# MCU.net
KiCad netlist of a schematic drawn in Altium Designer
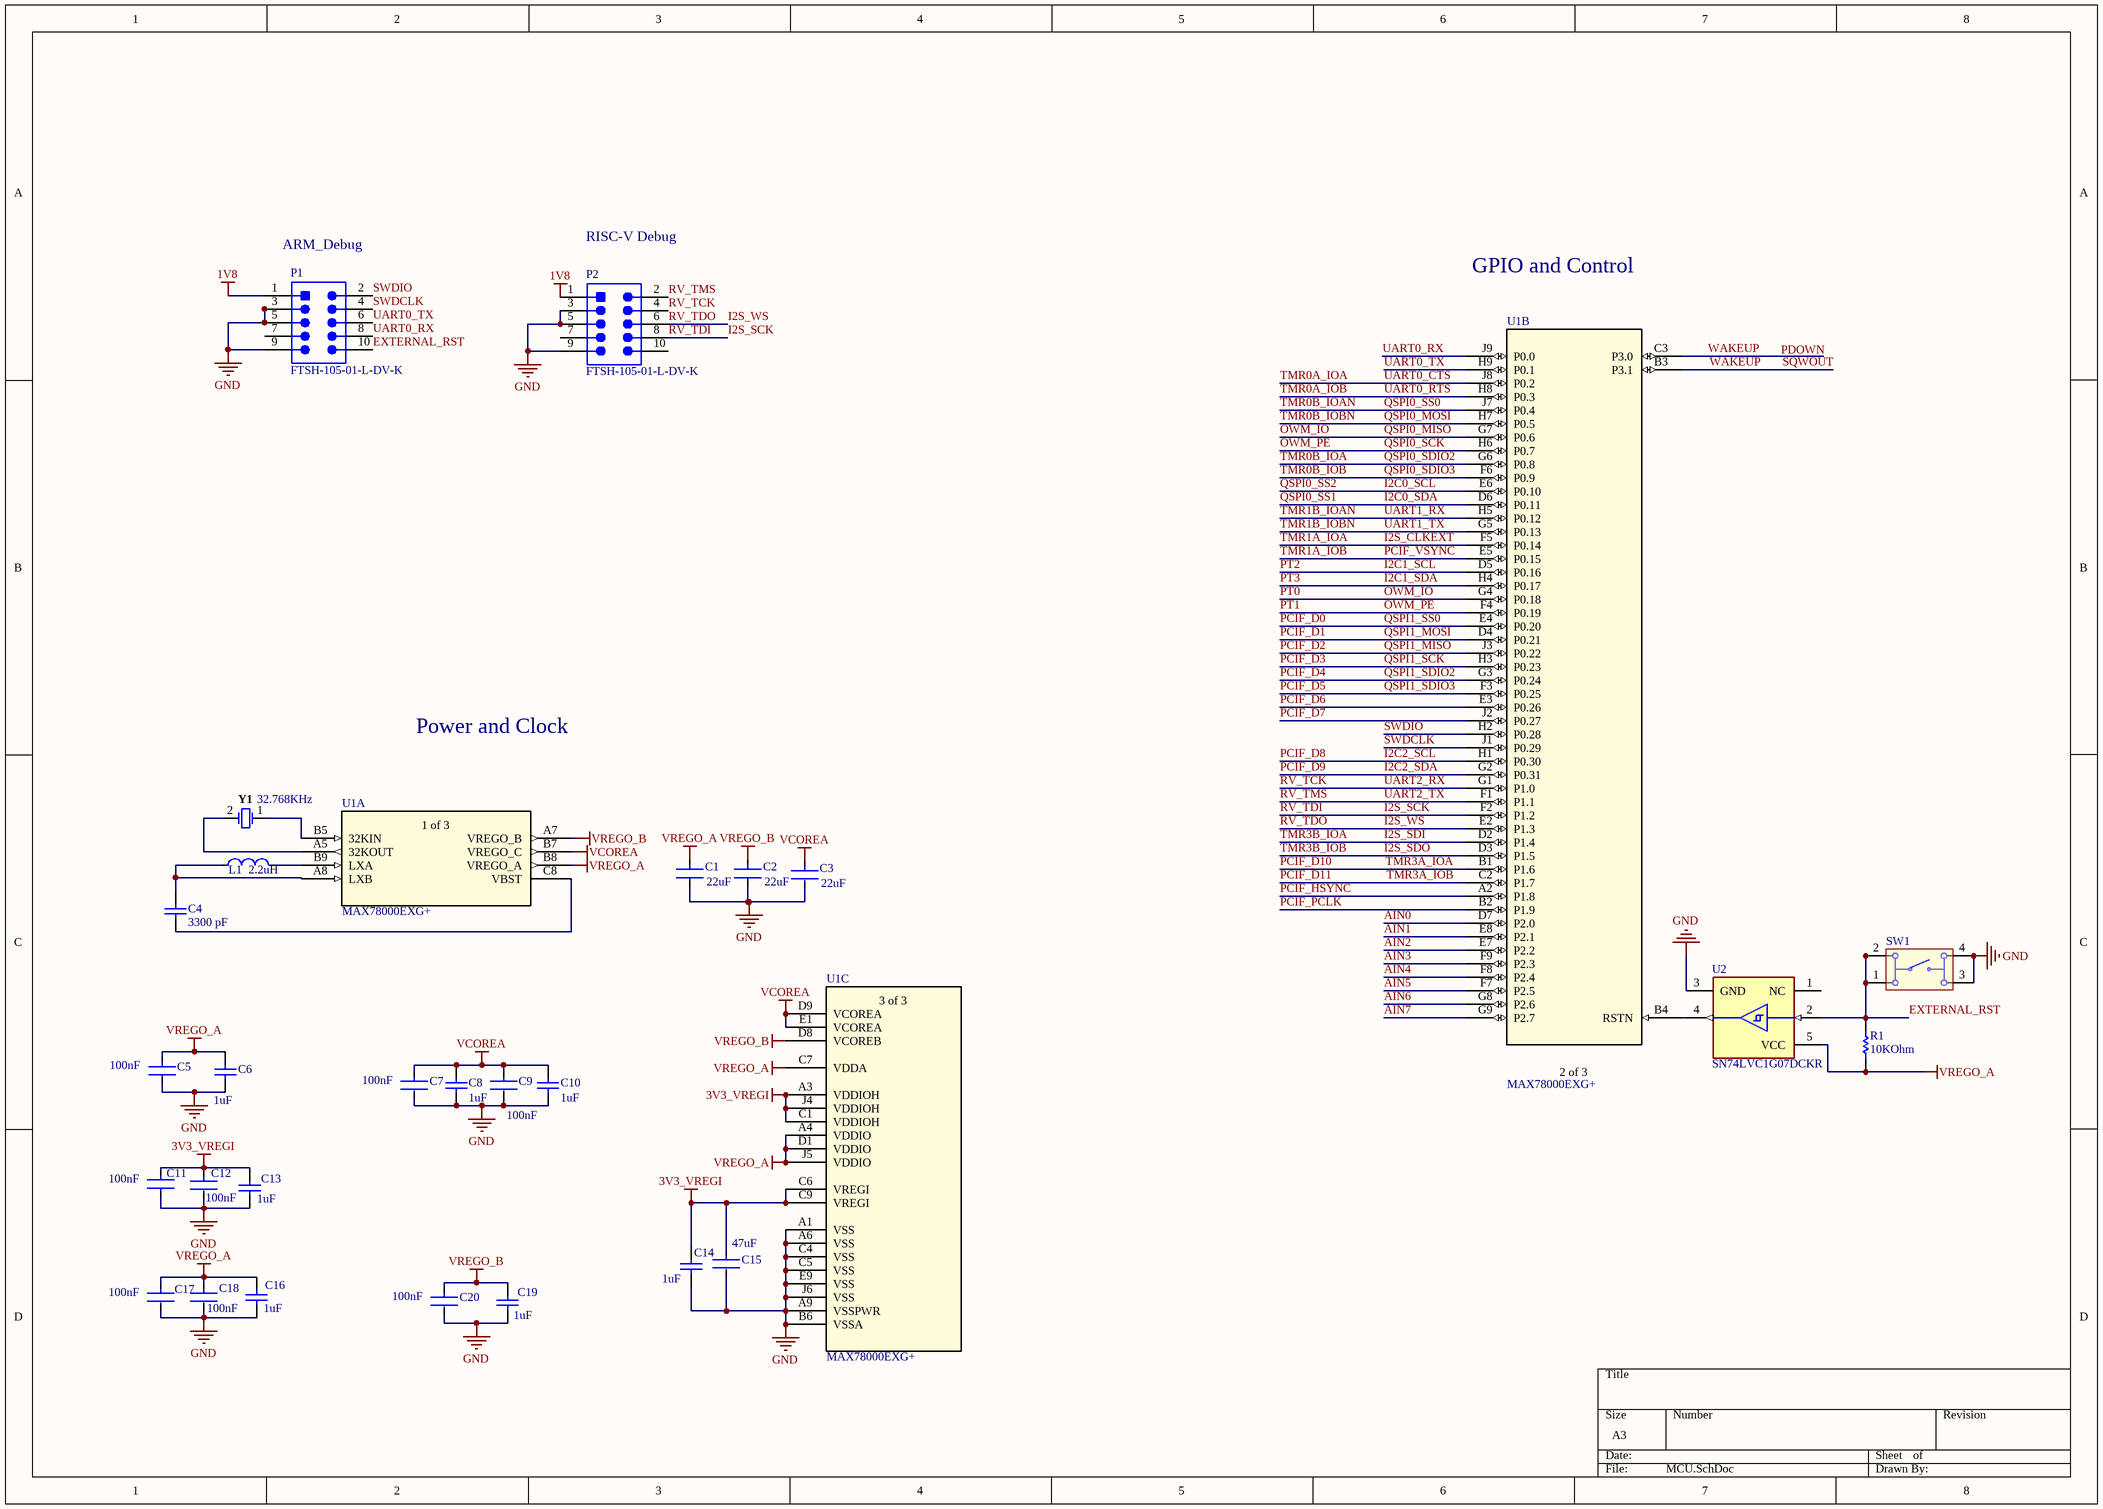
[diagram p0: MCU.SchDoc]

(export (version "E")
  (design (tool "Eeschema 10.0.6"))
  (components
    (comp (ref "C1")
      (value "CL10A226MO7JZNC")
      (footprint "FP-CL10-IPC_A")
      (description "Cap Ceramic 22uF 16V X5R ±20% Pad SMD 0603 +85°C T/R")
      (fields (field (name "CAPACITANCE") "22uF") (field (name "TOLERANCE") "20%"))
      (libsource (lib "Altium Content Vault") (part "b4654b650e69147ec39a6b967a45e02"))
    )
    (comp (ref "C2")
      (value "CL10A226MO7JZNC")
      (footprint "FP-CL10-IPC_A")
      (description "Cap Ceramic 22uF 16V X5R ±20% Pad SMD 0603 +85°C T/R")
      (fields (field (name "CAPACITANCE") "22uF") (field (name "TOLERANCE") "20%"))
      (libsource (lib "Altium Content Vault") (part "b4654b650e69147ec39a6b967a45e02"))
    )
    (comp (ref "C3")
      (value "CL10A226MO7JZNC")
      (footprint "FP-CL10-IPC_A")
      (description "Cap Ceramic 22uF 16V X5R ±20% Pad SMD 0603 +85°C T/R")
      (fields (field (name "CAPACITANCE") "22uF") (field (name "TOLERANCE") "20%"))
      (libsource (lib "Altium Content Vault") (part "b4654b650e69147ec39a6b967a45e02"))
    )
    (comp (ref "C4")
      (value "3300 pF")
      (footprint "CAPC1005X55X25ML05T10")
      (fields (field (name "MANUFACTURER") "Murata") (field (name "PART NUMBER") "GRM155R71H332KA01D"))
      (libsource (lib "Altium Content Vault") (part "CAP"))
    )
    (comp (ref "C5")
      (value "GRM033R61C104KE14D")
      (footprint "FP-GRM033-0_03-MFG")
      (description "Chip Multilayer Ceramic Capacitors for General Purpose, 0201, 0.10uF, X5R, 15%, 10%, 16V")
      (fields (field (name "TOLERANCE") "10%") (field (name "CAPACITANCE") "100nF"))
      (libsource (lib "Altium Content Vault") (part "b4654b650e69147ec39a6b967a45e02"))
    )
    (comp (ref "C6")
      (value "1uF")
      (footprint "CAPC1005X60X30LL05T10")
      (fields (field (name "PART NUMBER") "C0402C105K8PAC7867") (field (name "MANUFACTURER") "Kemet"))
      (libsource (lib "Altium Content Vault") (part "CAP"))
    )
    (comp (ref "C7")
      (value "GRM033R61C104KE14D")
      (footprint "FP-GRM033-0_03-MFG")
      (description "Chip Multilayer Ceramic Capacitors for General Purpose, 0201, 0.10uF, X5R, 15%, 10%, 16V")
      (fields (field (name "TOLERANCE") "10%") (field (name "CAPACITANCE") "100nF"))
      (libsource (lib "Altium Content Vault") (part "b4654b650e69147ec39a6b967a45e02"))
    )
    (comp (ref "C8")
      (value "1uF")
      (footprint "CAPC1005X60X30LL05T10")
      (fields (field (name "PART NUMBER") "C0402C105K8PAC7867") (field (name "MANUFACTURER") "Kemet"))
      (libsource (lib "Altium Content Vault") (part "CAP"))
    )
    (comp (ref "C9")
      (value "GRM033R61C104KE14D")
      (footprint "FP-GRM033-0_03-MFG")
      (description "Chip Multilayer Ceramic Capacitors for General Purpose, 0201, 0.10uF, X5R, 15%, 10%, 16V")
      (fields (field (name "TOLERANCE") "10%") (field (name "CAPACITANCE") "100nF"))
      (libsource (lib "Altium Content Vault") (part "b4654b650e69147ec39a6b967a45e02"))
    )
    (comp (ref "C10")
      (value "1uF")
      (footprint "CAPC1005X60X30LL05T10")
      (fields (field (name "PART NUMBER") "C0402C105K8PAC7867") (field (name "MANUFACTURER") "Kemet"))
      (libsource (lib "Altium Content Vault") (part "CAP"))
    )
    (comp (ref "C11")
      (value "GRM033R61C104KE14D")
      (footprint "FP-GRM033-0_03-MFG")
      (description "Chip Multilayer Ceramic Capacitors for General Purpose, 0201, 0.10uF, X5R, 15%, 10%, 16V")
      (fields (field (name "TOLERANCE") "10%") (field (name "CAPACITANCE") "100nF"))
      (libsource (lib "Altium Content Vault") (part "b4654b650e69147ec39a6b967a45e02"))
    )
    (comp (ref "C12")
      (value "GRM033R61C104KE14D")
      (footprint "FP-GRM033-0_03-MFG")
      (description "Chip Multilayer Ceramic Capacitors for General Purpose, 0201, 0.10uF, X5R, 15%, 10%, 16V")
      (fields (field (name "TOLERANCE") "10%") (field (name "CAPACITANCE") "100nF"))
      (libsource (lib "Altium Content Vault") (part "b4654b650e69147ec39a6b967a45e02"))
    )
    (comp (ref "C13")
      (value "1uF")
      (footprint "CAPC1005X60X30LL05T10")
      (fields (field (name "PART NUMBER") "C0402C105K8PAC7867") (field (name "MANUFACTURER") "Kemet"))
      (libsource (lib "Altium Content Vault") (part "CAP"))
    )
    (comp (ref "C14")
      (value "1uF")
      (footprint "CAPC1005X60X30LL05T10")
      (fields (field (name "PART NUMBER") "C0402C105K8PAC7867") (field (name "MANUFACTURER") "Kemet"))
      (libsource (lib "Altium Content Vault") (part "CAP"))
    )
    (comp (ref "C15")
      (value "GRM21BR61A476ME15K")
      (footprint "FP-GRM21B-0_2-e0_2_0_7-IPC_B")
      (description "Chip Multilayer Ceramic Capacitors for General Purpose, 0805, 47uF, X5R, 15%, 20%, 10V")
      (fields (field (name "TOLERANCE") "20%") (field (name "CAPACITANCE") "47uF"))
      (libsource (lib "Altium Content Vault") (part "b4654b650e69147ec39a6b967a45e02"))
    )
    (comp (ref "C16")
      (value "1uF")
      (footprint "CAPC1005X60X30LL05T10")
      (fields (field (name "PART NUMBER") "C0402C105K8PAC7867") (field (name "MANUFACTURER") "Kemet"))
      (libsource (lib "Altium Content Vault") (part "CAP"))
    )
    (comp (ref "C17")
      (value "GRM033R61C104KE14D")
      (footprint "FP-GRM033-0_03-MFG")
      (description "Chip Multilayer Ceramic Capacitors for General Purpose, 0201, 0.10uF, X5R, 15%, 10%, 16V")
      (fields (field (name "TOLERANCE") "10%") (field (name "CAPACITANCE") "100nF"))
      (libsource (lib "Altium Content Vault") (part "b4654b650e69147ec39a6b967a45e02"))
    )
    (comp (ref "C18")
      (value "GRM033R61C104KE14D")
      (footprint "FP-GRM033-0_03-MFG")
      (description "Chip Multilayer Ceramic Capacitors for General Purpose, 0201, 0.10uF, X5R, 15%, 10%, 16V")
      (fields (field (name "TOLERANCE") "10%") (field (name "CAPACITANCE") "100nF"))
      (libsource (lib "Altium Content Vault") (part "b4654b650e69147ec39a6b967a45e02"))
    )
    (comp (ref "C19")
      (value "1uF")
      (footprint "CAPC1005X60X30LL05T10")
      (fields (field (name "PART NUMBER") "C0402C105K8PAC7867") (field (name "MANUFACTURER") "Kemet"))
      (libsource (lib "Altium Content Vault") (part "CAP"))
    )
    (comp (ref "C20")
      (value "GRM033R61C104KE14D")
      (footprint "FP-GRM033-0_03-MFG")
      (description "Chip Multilayer Ceramic Capacitors for General Purpose, 0201, 0.10uF, X5R, 15%, 10%, 16V")
      (fields (field (name "TOLERANCE") "10%") (field (name "CAPACITANCE") "100nF"))
      (libsource (lib "Altium Content Vault") (part "b4654b650e69147ec39a6b967a45e02"))
    )
    (comp (ref "L1")
      (value "MLP2012H2R2MT0S1")
      (footprint "FP-MLP2012M-IPC_C")
      (description "Shielded Multilayer Inductor 2.2uH ±20% 1000mA 195mΩ SMD 0805")
      (fields (field (name "TOLERANCE") "20%") (field (name "INDUCTANCE") "2.2uH"))
      (libsource (lib "Altium Content Vault") (part "725321dda6339637d4d059423bc1c3c"))
    )
    (comp (ref "P1")
      (value "FTSH-105-01-L-DV-K")
      (footprint "SMTC-FTSH-105-01-L-DV-K_V")
      (description "Male Header, Pitch 1.27 mm, 2 x 5 Position, Height 6.25 mm")
      (fields (field (name "MANUFACTURER") "Samtec"))
      (libsource (lib "Altium Content Vault") (part "CN-2P-M-R10"))
    )
    (comp (ref "P2")
      (value "FTSH-105-01-L-DV-K")
      (footprint "SMTC-FTSH-105-01-L-DV-K_V")
      (description "Male Header, Pitch 1.27 mm, 2 x 5 Position, Height 6.25 mm")
      (fields (field (name "MANUFACTURER") "Samtec"))
      (libsource (lib "Altium Content Vault") (part "CN-2P-M-R10"))
    )
    (comp (ref "R1")
      (value "ERJ3EKF1002V")
      (footprint "RESC1609X55X30LL15T15")
      (description "Chip Resistor, 10 KOhm, +/- 1%, 0.1 W, -55 to 155 degC, 0603 (1608 Metric), RoHS, Tape and Reel")
      (fields
        (field (name "RESISTANCE") "10KOhm")
        (field (name "TOLERANCE") "1%")
        (field (name "MANUFACTURER") "Panasonic")
      )
      (libsource (lib "Altium Content Vault") (part "RES-2"))
    )
    (comp (ref "SW1")
      (value "430481025816")
      (footprint "430481025816")
      (description "WS-TASV SMD Tact Switch 6X6 mm")
      (fields (field (name "MANUFACTURER") "Wuerth Elektronik"))
      (libsource (lib "Altium Content Vault") (part "WE-TACT-SW-4_A"))
    )
    (comp (ref "U1")
      (value "MAX78000EXG+")
      (footprint "21-0735_MXM")
      (description "No Description Available")
      (fields (field (name "COPYRIGHT") "Copyright (C) 2018 Accelerated Designs. All rights reserved"))
      (libsource (lib "2021-06-08_17-56-01") (part "MAX78000EXG+"))
    )
    (comp (ref "U2")
      (value "SN74LVC1G07DCKR")
      (footprint "FP-DCK0005A-IPC_C")
      (description "IC BUFF/DVR NON-INVERT SC70-5")
      (libsource (lib "Altium Content Vault") (part "8ab337023d36144ede9cc3383aed264"))
    )
    (comp (ref "Y1")
      (value "ABS07-120-32.768KHZ-T")
      (footprint "ABRA-ABS07_A_V")
      (description "Tuning Fork Crystal, 32.768 KHz, +/- 20 ppm, -40 to 85 degC, 2-Pin SMD, RoHS, Tape and Reel")
      (fields
        (field (name "FREQUENCY") "32.768KHz")
        (field (name "MANUFACTURER") "Abracon")
        (field (name "TOLERANCE") "20ppm")
      )
      (libsource (lib "Altium Content Vault") (part "XTAL-1-2-2"))
    )
  )
  (nets
    (net (code "1") (name "/AIN0") (class "Default")
      (node (ref "U1") (pin "D7") (pinfunction "P2.0_D7") (pintype "bidirectional"))
    )
    (net (code "2") (name "/AIN1") (class "Default")
      (node (ref "U1") (pin "E8") (pinfunction "P2.1_E8") (pintype "bidirectional"))
    )
    (net (code "3") (name "/AIN2") (class "Default")
      (node (ref "U1") (pin "E7") (pinfunction "P2.2_E7") (pintype "bidirectional"))
    )
    (net (code "4") (name "/AIN3") (class "Default")
      (node (ref "U1") (pin "F9") (pinfunction "P2.3_F9") (pintype "bidirectional"))
    )
    (net (code "5") (name "/AIN4") (class "Default")
      (node (ref "U1") (pin "F8") (pinfunction "P2.4_F8") (pintype "bidirectional"))
    )
    (net (code "6") (name "/AIN5") (class "Default")
      (node (ref "U1") (pin "F7") (pinfunction "P2.5_F7") (pintype "bidirectional"))
    )
    (net (code "7") (name "/AIN6") (class "Default")
      (node (ref "U1") (pin "G8") (pinfunction "P2.6_G8") (pintype "bidirectional"))
    )
    (net (code "8") (name "/AIN7") (class "Default")
      (node (ref "U1") (pin "G9") (pinfunction "P2.7_G9") (pintype "bidirectional"))
    )
    (net (code "9") (name "/EXTERNAL_RST") (class "Default")
      (node (ref "P1") (pin "10") (pinfunction "10_10") (pintype "passive"))
      (node (ref "R1") (pin "2") (pinfunction "2_2") (pintype "passive"))
      (node (ref "SW1") (pin "1") (pinfunction "1_1") (pintype "passive"))
      (node (ref "SW1") (pin "2") (pinfunction "2_2") (pintype "passive"))
      (node (ref "U2") (pin "2") (pinfunction "A_2") (pintype "input"))
    )
    (net (code "10") (name "/I2C0_SCL") (class "Default")
      (node (ref "U1") (pin "E6") (pinfunction "P0.10_E6") (pintype "bidirectional"))
    )
    (net (code "11") (name "/I2C0_SDA") (class "Default")
      (node (ref "U1") (pin "D6") (pinfunction "P0.11_D6") (pintype "bidirectional"))
    )
    (net (code "12") (name "/I2C1_SCL") (class "Default")
      (node (ref "U1") (pin "D5") (pinfunction "P0.16_D5") (pintype "bidirectional"))
    )
    (net (code "13") (name "/I2C1_SDA") (class "Default")
      (node (ref "U1") (pin "H4") (pinfunction "P0.17_H4") (pintype "bidirectional"))
    )
    (net (code "14") (name "/I2C2_SCL") (class "Default")
      (node (ref "U1") (pin "H1") (pinfunction "P0.30_H1") (pintype "bidirectional"))
    )
    (net (code "15") (name "/I2C2_SDA") (class "Default")
      (node (ref "U1") (pin "G2") (pinfunction "P0.31_G2") (pintype "bidirectional"))
    )
    (net (code "16") (name "/I2S_CLKEXT") (class "Default")
      (node (ref "U1") (pin "F5") (pinfunction "P0.14_F5") (pintype "bidirectional"))
    )
    (net (code "17") (name "/I2S_SCK") (class "Default")
      (node (ref "P2") (pin "8") (pinfunction "8_8") (pintype "passive"))
      (node (ref "U1") (pin "F2") (pinfunction "P1.2_F2") (pintype "bidirectional"))
    )
    (net (code "18") (name "/I2S_SDI") (class "Default")
      (node (ref "U1") (pin "D2") (pinfunction "P1.4_D2") (pintype "bidirectional"))
    )
    (net (code "19") (name "/I2S_SDO") (class "Default")
      (node (ref "U1") (pin "D3") (pinfunction "P1.5_D3") (pintype "bidirectional"))
    )
    (net (code "20") (name "/I2S_WS") (class "Default")
      (node (ref "P2") (pin "6") (pinfunction "6_6") (pintype "passive"))
      (node (ref "U1") (pin "E2") (pinfunction "P1.3_E2") (pintype "bidirectional"))
    )
    (net (code "21") (name "/OWM_IO") (class "Default")
      (node (ref "U1") (pin "G4") (pinfunction "P0.18_G4") (pintype "bidirectional"))
      (node (ref "U1") (pin "G7") (pinfunction "P0.6_G7") (pintype "bidirectional"))
    )
    (net (code "22") (name "/OWM_PE") (class "Default")
      (node (ref "U1") (pin "F4") (pinfunction "P0.19_F4") (pintype "bidirectional"))
      (node (ref "U1") (pin "H6") (pinfunction "P0.7_H6") (pintype "bidirectional"))
    )
    (net (code "23") (name "/PCIF_D0") (class "Default")
      (node (ref "U1") (pin "E4") (pinfunction "P0.20_E4") (pintype "bidirectional"))
    )
    (net (code "24") (name "/PCIF_D1") (class "Default")
      (node (ref "U1") (pin "D4") (pinfunction "P0.21_D4") (pintype "bidirectional"))
    )
    (net (code "25") (name "/PCIF_D2") (class "Default")
      (node (ref "U1") (pin "J3") (pinfunction "P0.22_J3") (pintype "bidirectional"))
    )
    (net (code "26") (name "/PCIF_D3") (class "Default")
      (node (ref "U1") (pin "H3") (pinfunction "P0.23_H3") (pintype "bidirectional"))
    )
    (net (code "27") (name "/PCIF_D4") (class "Default")
      (node (ref "U1") (pin "G3") (pinfunction "P0.24_G3") (pintype "bidirectional"))
    )
    (net (code "28") (name "/PCIF_D5") (class "Default")
      (node (ref "U1") (pin "F3") (pinfunction "P0.25_F3") (pintype "bidirectional"))
    )
    (net (code "29") (name "/PCIF_D6") (class "Default")
      (node (ref "U1") (pin "E3") (pinfunction "P0.26_E3") (pintype "bidirectional"))
    )
    (net (code "30") (name "/PCIF_D7") (class "Default")
      (node (ref "U1") (pin "J2") (pinfunction "P0.27_J2") (pintype "bidirectional"))
    )
    (net (code "31") (name "/PCIF_D10") (class "Default")
      (node (ref "U1") (pin "B1") (pinfunction "P1.6_B1") (pintype "bidirectional"))
    )
    (net (code "32") (name "/PCIF_D11") (class "Default")
      (node (ref "U1") (pin "C2") (pinfunction "P1.7_C2") (pintype "bidirectional"))
    )
    (net (code "33") (name "/PCIF_HSYNC") (class "Default")
      (node (ref "U1") (pin "A2") (pinfunction "P1.8_A2") (pintype "bidirectional"))
    )
    (net (code "34") (name "/PCIF_PCLK") (class "Default")
      (node (ref "U1") (pin "B2") (pinfunction "P1.9_B2") (pintype "bidirectional"))
    )
    (net (code "35") (name "/PCIF_VSYNC") (class "Default")
      (node (ref "U1") (pin "E5") (pinfunction "P0.15_E5") (pintype "bidirectional"))
    )
    (net (code "37") (name "/QSPI0_MOSI") (class "Default")
      (node (ref "U1") (pin "H7") (pinfunction "P0.5_H7") (pintype "bidirectional"))
    )
    (net (code "38") (name "/QSPI0_SDIO2") (class "Default")
      (node (ref "U1") (pin "G6") (pinfunction "P0.8_G6") (pintype "bidirectional"))
    )
    (net (code "39") (name "/QSPI0_SDIO3") (class "Default")
      (node (ref "U1") (pin "F6") (pinfunction "P0.9_F6") (pintype "bidirectional"))
    )
    (net (code "40") (name "/QSPI0_SS0") (class "Default")
      (node (ref "U1") (pin "J7") (pinfunction "P0.4_J7") (pintype "bidirectional"))
    )
    (net (code "41") (name "/RV_TCK") (class "Default")
      (node (ref "P2") (pin "4") (pinfunction "4_4") (pintype "passive"))
      (node (ref "U1") (pin "G1") (pinfunction "P1.0_G1") (pintype "bidirectional"))
    )
    (net (code "42") (name "/RV_TMS") (class "Default")
      (node (ref "P2") (pin "2") (pinfunction "2_2") (pintype "passive"))
      (node (ref "U1") (pin "F1") (pinfunction "P1.1_F1") (pintype "bidirectional"))
    )
    (net (code "43") (name "/SQWOUT") (class "Default")
      (node (ref "U1") (pin "B3") (pinfunction "P3.1_B3") (pintype "bidirectional"))
      (node (ref "U1") (pin "C3") (pinfunction "P3.0_C3") (pintype "bidirectional"))
    )
    (net (code "44") (name "/SWDCLK") (class "Default")
      (node (ref "P1") (pin "4") (pinfunction "4_4") (pintype "passive"))
      (node (ref "U1") (pin "J1") (pinfunction "P0.29_J1") (pintype "bidirectional"))
    )
    (net (code "45") (name "/SWDIO") (class "Default")
      (node (ref "P1") (pin "2") (pinfunction "2_2") (pintype "passive"))
      (node (ref "U1") (pin "H2") (pinfunction "P0.28_H2") (pintype "bidirectional"))
    )
    (net (code "46") (name "/TMR0A_IOA") (class "Default")
      (node (ref "U1") (pin "J8") (pinfunction "P0.2_J8") (pintype "bidirectional"))
    )
    (net (code "47") (name "/TMR0A_IOB") (class "Default")
      (node (ref "U1") (pin "H8") (pinfunction "P0.3_H8") (pintype "bidirectional"))
    )
    (net (code "48") (name "/TMR1B_IOAN") (class "Default")
      (node (ref "U1") (pin "H5") (pinfunction "P0.12_H5") (pintype "bidirectional"))
    )
    (net (code "49") (name "/TMR1B_IOBN") (class "Default")
      (node (ref "U1") (pin "G5") (pinfunction "P0.13_G5") (pintype "bidirectional"))
    )
    (net (code "50") (name "/UART0_RX") (class "Default")
      (node (ref "P1") (pin "8") (pinfunction "8_8") (pintype "passive"))
      (node (ref "U1") (pin "J9") (pinfunction "P0.0_J9") (pintype "bidirectional"))
    )
    (net (code "51") (name "/UART0_TX") (class "Default")
      (node (ref "P1") (pin "6") (pinfunction "6_6") (pintype "passive"))
      (node (ref "U1") (pin "H9") (pinfunction "P0.1_H9") (pintype "bidirectional"))
    )
    (net (code "52") (name "1V8") (class "Default")
      (node (ref "P1") (pin "1") (pinfunction "1_1") (pintype "passive"))
      (node (ref "P2") (pin "1") (pinfunction "1_1") (pintype "passive"))
    )
    (net (code "53") (name "3V3_VREGI") (class "Default")
      (node (ref "C11") (pin "1") (pinfunction "1_1") (pintype "passive"))
      (node (ref "C12") (pin "1") (pinfunction "1_1") (pintype "passive"))
      (node (ref "C13") (pin "2") (pinfunction "2_2") (pintype "passive"))
      (node (ref "C14") (pin "2") (pinfunction "2_2") (pintype "passive"))
      (node (ref "C15") (pin "1") (pinfunction "1_1") (pintype "passive"))
      (node (ref "U1") (pin "A3") (pinfunction "VDDIOH_A3") (pintype "power_in"))
      (node (ref "U1") (pin "C1") (pinfunction "VDDIOH_C1") (pintype "power_in"))
      (node (ref "U1") (pin "C6") (pinfunction "VREGI_C6") (pintype "power_in"))
      (node (ref "U1") (pin "C9") (pinfunction "VREGI_C9") (pintype "power_in"))
      (node (ref "U1") (pin "J4") (pinfunction "VDDIOH_J4") (pintype "power_in"))
    )
    (net (code "54") (name "GND") (class "Default")
      (node (ref "C1") (pin "2") (pinfunction "2_2") (pintype "passive"))
      (node (ref "C10") (pin "1") (pinfunction "1_1") (pintype "passive"))
      (node (ref "C11") (pin "2") (pinfunction "2_2") (pintype "passive"))
      (node (ref "C12") (pin "2") (pinfunction "2_2") (pintype "passive"))
      (node (ref "C13") (pin "1") (pinfunction "1_1") (pintype "passive"))
      (node (ref "C14") (pin "1") (pinfunction "1_1") (pintype "passive"))
      (node (ref "C15") (pin "2") (pinfunction "2_2") (pintype "passive"))
      (node (ref "C16") (pin "1") (pinfunction "1_1") (pintype "passive"))
      (node (ref "C17") (pin "2") (pinfunction "2_2") (pintype "passive"))
      (node (ref "C18") (pin "2") (pinfunction "2_2") (pintype "passive"))
      (node (ref "C19") (pin "1") (pinfunction "1_1") (pintype "passive"))
      (node (ref "C2") (pin "2") (pinfunction "2_2") (pintype "passive"))
      (node (ref "C20") (pin "2") (pinfunction "2_2") (pintype "passive"))
      (node (ref "C3") (pin "2") (pinfunction "2_2") (pintype "passive"))
      (node (ref "C5") (pin "2") (pinfunction "2_2") (pintype "passive"))
      (node (ref "C6") (pin "1") (pinfunction "1_1") (pintype "passive"))
      (node (ref "C7") (pin "2") (pinfunction "2_2") (pintype "passive"))
      (node (ref "C8") (pin "1") (pinfunction "1_1") (pintype "passive"))
      (node (ref "C9") (pin "2") (pinfunction "2_2") (pintype "passive"))
      (node (ref "P1") (pin "3") (pinfunction "3_3") (pintype "passive"))
      (node (ref "P1") (pin "5") (pinfunction "5_5") (pintype "passive"))
      (node (ref "P1") (pin "9") (pinfunction "9_9") (pintype "passive"))
      (node (ref "P2") (pin "3") (pinfunction "3_3") (pintype "passive"))
      (node (ref "P2") (pin "5") (pinfunction "5_5") (pintype "passive"))
      (node (ref "P2") (pin "9") (pinfunction "9_9") (pintype "passive"))
      (node (ref "SW1") (pin "3") (pinfunction "3_3") (pintype "passive"))
      (node (ref "SW1") (pin "4") (pinfunction "4_4") (pintype "passive"))
      (node (ref "U1") (pin "A1") (pinfunction "VSS_A1") (pintype "passive"))
      (node (ref "U1") (pin "A6") (pinfunction "VSS_A6") (pintype "passive"))
      (node (ref "U1") (pin "A9") (pinfunction "VSSPWR_A9") (pintype "passive"))
      (node (ref "U1") (pin "B6") (pinfunction "VSSA_B6") (pintype "passive"))
      (node (ref "U1") (pin "C4") (pinfunction "VSS_C4") (pintype "passive"))
      (node (ref "U1") (pin "C5") (pinfunction "VSS_C5") (pintype "passive"))
      (node (ref "U1") (pin "E9") (pinfunction "VSS_E9") (pintype "passive"))
      (node (ref "U1") (pin "J6") (pinfunction "VSS_J6") (pintype "passive"))
      (node (ref "U2") (pin "3") (pinfunction "GND_3") (pintype "power_in"))
    )
    (net (code "55") (name "Net-(U1A-32KIN)") (class "Default")
      (node (ref "U1") (pin "B5") (pinfunction "32KIN_B5") (pintype "input"))
      (node (ref "Y1") (pin "1") (pinfunction "1_1") (pintype "passive"))
    )
    (net (code "56") (name "Net-(U1A-32KOUT)") (class "Default")
      (node (ref "U1") (pin "A5") (pinfunction "32KOUT_A5") (pintype "output"))
      (node (ref "Y1") (pin "2") (pinfunction "2_2") (pintype "passive"))
    )
    (net (code "57") (name "Net-(U1A-LXA)") (class "Default")
      (node (ref "L1") (pin "2") (pinfunction "2_2") (pintype "passive"))
      (node (ref "U1") (pin "B9") (pinfunction "LXA_B9") (pintype "input"))
    )
    (net (code "58") (name "Net-(U1A-LXB)") (class "Default")
      (node (ref "C4") (pin "2") (pinfunction "2_2") (pintype "passive"))
      (node (ref "L1") (pin "1") (pinfunction "1_1") (pintype "passive"))
      (node (ref "U1") (pin "A8") (pinfunction "LXB_A8") (pintype "input"))
    )
    (net (code "59") (name "Net-(U1A-VBST)") (class "Default")
      (node (ref "C4") (pin "1") (pinfunction "1_1") (pintype "passive"))
      (node (ref "U1") (pin "C8") (pinfunction "VBST_C8") (pintype "passive"))
    )
    (net (code "60") (name "Net-(U1B-RSTN)") (class "Default")
      (node (ref "U1") (pin "B4") (pinfunction "RSTN_B4") (pintype "input"))
      (node (ref "U2") (pin "4") (pinfunction "Y_4") (pintype "output"))
    )
    (net (code "61") (name "VCOREA") (class "Default")
      (node (ref "C10") (pin "2") (pinfunction "2_2") (pintype "passive"))
      (node (ref "C3") (pin "1") (pinfunction "1_1") (pintype "passive"))
      (node (ref "C7") (pin "1") (pinfunction "1_1") (pintype "passive"))
      (node (ref "C8") (pin "2") (pinfunction "2_2") (pintype "passive"))
      (node (ref "C9") (pin "1") (pinfunction "1_1") (pintype "passive"))
      (node (ref "U1") (pin "B7") (pinfunction "VREGO_C_B7") (pintype "output"))
      (node (ref "U1") (pin "D9") (pinfunction "VCOREA_D9") (pintype "power_in"))
      (node (ref "U1") (pin "E1") (pinfunction "VCOREA_E1") (pintype "power_in"))
    )
    (net (code "62") (name "VREGO_A") (class "Default")
      (node (ref "C1") (pin "1") (pinfunction "1_1") (pintype "passive"))
      (node (ref "C16") (pin "2") (pinfunction "2_2") (pintype "passive"))
      (node (ref "C17") (pin "1") (pinfunction "1_1") (pintype "passive"))
      (node (ref "C18") (pin "1") (pinfunction "1_1") (pintype "passive"))
      (node (ref "C5") (pin "1") (pinfunction "1_1") (pintype "passive"))
      (node (ref "C6") (pin "2") (pinfunction "2_2") (pintype "passive"))
      (node (ref "R1") (pin "1") (pinfunction "1_1") (pintype "passive"))
      (node (ref "U1") (pin "A4") (pinfunction "VDDIO_A4") (pintype "power_in"))
      (node (ref "U1") (pin "B8") (pinfunction "VREGO_A_B8") (pintype "output"))
      (node (ref "U1") (pin "C7") (pinfunction "VDDA_C7") (pintype "power_in"))
      (node (ref "U1") (pin "D1") (pinfunction "VDDIO_D1") (pintype "power_in"))
      (node (ref "U1") (pin "J5") (pinfunction "VDDIO_J5") (pintype "power_in"))
      (node (ref "U2") (pin "5") (pinfunction "VCC_5") (pintype "power_in"))
    )
    (net (code "63") (name "VREGO_B") (class "Default")
      (node (ref "C19") (pin "2") (pinfunction "2_2") (pintype "passive"))
      (node (ref "C2") (pin "1") (pinfunction "1_1") (pintype "passive"))
      (node (ref "C20") (pin "1") (pinfunction "1_1") (pintype "passive"))
      (node (ref "U1") (pin "A7") (pinfunction "VREGO_B_A7") (pintype "output"))
      (node (ref "U1") (pin "D8") (pinfunction "VCOREB_D8") (pintype "power_in"))
    )
    (net (code "64") (name "unconnected-(P1-Pad7)") (class "Default")
      (node (ref "P1") (pin "7") (pinfunction "7_7") (pintype "passive"))
    )
    (net (code "65") (name "unconnected-(P2-Pad7)") (class "Default")
      (node (ref "P2") (pin "7") (pinfunction "7_7") (pintype "passive"))
    )
    (net (code "66") (name "unconnected-(P2-Pad10)") (class "Default")
      (node (ref "P2") (pin "10") (pinfunction "10_10") (pintype "passive"))
    )
    (net (code "67") (name "unconnected-(U2-NC-Pad1)") (class "Default")
      (node (ref "U2") (pin "1") (pinfunction "NC_1") (pintype "passive"))
    )
  )
)
